# RelayExtension.net
KiCad netlist of a schematic drawn in Altium Designer
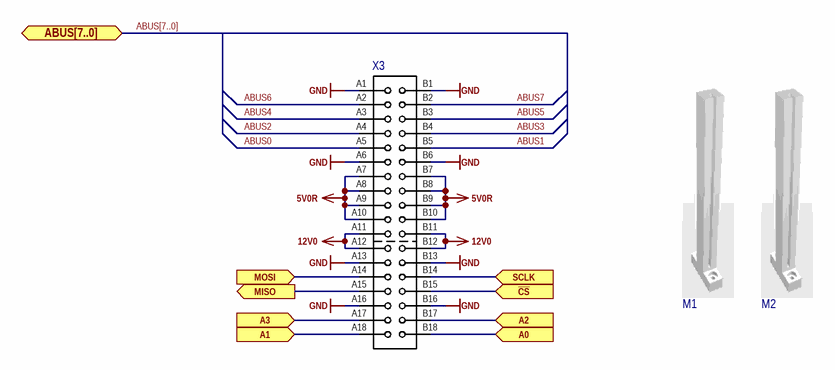
[diagram p0: RelayExtension.SchDoc]

(export (version "E")
  (design (tool "Eeschema 10.0.6"))
  (components
    (comp (ref "M1")
      (value "PCB Support")
      (footprint "PCB Tester Support")
      (fields
        (field (name "07. MANUFACTURER  PART NUMBER") "TBD")
        (field (name "13. CREATED DATE/NAME") "??? / Hören")
      )
      (libsource (lib "PCB-Tester-Board-V1") (part "PCB Tester Support"))
    )
    (comp (ref "M2")
      (value "PCB Support")
      (footprint "PCB Tester Support")
      (fields
        (field (name "07. MANUFACTURER  PART NUMBER") "TBD")
        (field (name "13. CREATED DATE/NAME") "??? / Hören")
      )
      (libsource (lib "PCB-Tester-Board-V1") (part "PCB Tester Support"))
    )
    (comp (ref "X3")
      (value "X")
      (footprint "PCIE-036-02-F-D-TH")
      (description "CONN PCI EXP FMALE 36POS 0.039")
      (fields
        (field (name "02. DISTRIBUTOR PART NUMBER") "SAM10625-ND")
        (field (name "07. MANUFACTURER  PART NUMBER") "PCIE-036-02-F-D-TH")
        (field (name "13. CREATED DATE/NAME") "??? / Hören")
      )
      (libsource (lib "Connectors") (part "PCIE-036-02-F-D-TH"))
    )
  )
  (nets
    (net (code "1") (name "/A0") (class "Default")
      (node (ref "X3") (pin "B18") (pinfunction "B18_B18") (pintype "passive"))
    )
    (net (code "2") (name "/A1") (class "Default")
      (node (ref "X3") (pin "A18") (pinfunction "A18_A18") (pintype "passive"))
    )
    (net (code "3") (name "/A2") (class "Default")
      (node (ref "X3") (pin "B17") (pinfunction "B17_B17") (pintype "passive"))
    )
    (net (code "4") (name "/A3") (class "Default")
      (node (ref "X3") (pin "A17") (pinfunction "A17_A17") (pintype "passive"))
    )
    (net (code "5") (name "/ABUS0") (class "Default")
      (node (ref "X3") (pin "A5") (pinfunction "A5_A5") (pintype "passive"))
    )
    (net (code "6") (name "/ABUS1") (class "Default")
      (node (ref "X3") (pin "B5") (pinfunction "B5_B5") (pintype "passive"))
    )
    (net (code "7") (name "/ABUS2") (class "Default")
      (node (ref "X3") (pin "A4") (pinfunction "A4_A4") (pintype "passive"))
    )
    (net (code "8") (name "/ABUS3") (class "Default")
      (node (ref "X3") (pin "B4") (pinfunction "B4_B4") (pintype "passive"))
    )
    (net (code "9") (name "/ABUS4") (class "Default")
      (node (ref "X3") (pin "A3") (pinfunction "A3_A3") (pintype "passive"))
    )
    (net (code "10") (name "/ABUS5") (class "Default")
      (node (ref "X3") (pin "B3") (pinfunction "B3_B3") (pintype "passive"))
    )
    (net (code "11") (name "/ABUS6") (class "Default")
      (node (ref "X3") (pin "A2") (pinfunction "A2_A2") (pintype "passive"))
    )
    (net (code "12") (name "/ABUS7") (class "Default")
      (node (ref "X3") (pin "B2") (pinfunction "B2_B2") (pintype "passive"))
    )
    (net (code "14") (name "/CS") (class "Default")
      (node (ref "X3") (pin "B15") (pinfunction "B15_B15") (pintype "passive"))
    )
    (net (code "15") (name "/MISO") (class "Default")
      (node (ref "X3") (pin "A15") (pinfunction "A15_A15") (pintype "passive"))
    )
    (net (code "16") (name "/MOSI") (class "Default")
      (node (ref "X3") (pin "A14") (pinfunction "A14_A14") (pintype "passive"))
    )
    (net (code "17") (name "/SCLK") (class "Default")
      (node (ref "X3") (pin "B14") (pinfunction "B14_B14") (pintype "passive"))
    )
    (net (code "18") (name "5V0R") (class "Default")
      (node (ref "X3") (pin "A10") (pinfunction "A10_A10") (pintype "passive"))
      (node (ref "X3") (pin "A7") (pinfunction "A7_A7") (pintype "passive"))
      (node (ref "X3") (pin "A8") (pinfunction "A8_A8") (pintype "passive"))
      (node (ref "X3") (pin "A9") (pinfunction "A9_A9") (pintype "passive"))
      (node (ref "X3") (pin "B10") (pinfunction "B10_B10") (pintype "passive"))
      (node (ref "X3") (pin "B7") (pinfunction "B7_B7") (pintype "passive"))
      (node (ref "X3") (pin "B8") (pinfunction "B8_B8") (pintype "passive"))
      (node (ref "X3") (pin "B9") (pinfunction "B9_B9") (pintype "passive"))
    )
    (net (code "19") (name "12V0") (class "Default")
      (node (ref "X3") (pin "A11") (pinfunction "A11_A11") (pintype "passive"))
      (node (ref "X3") (pin "A12") (pinfunction "A12_A12") (pintype "passive"))
      (node (ref "X3") (pin "B11") (pinfunction "B11_B11") (pintype "passive"))
      (node (ref "X3") (pin "B12") (pinfunction "B12_B12") (pintype "passive"))
    )
    (net (code "20") (name "GND") (class "Default")
      (node (ref "X3") (pin "A1") (pinfunction "A1_A1") (pintype "passive"))
      (node (ref "X3") (pin "A13") (pinfunction "A13_A13") (pintype "passive"))
      (node (ref "X3") (pin "A16") (pinfunction "A16_A16") (pintype "passive"))
      (node (ref "X3") (pin "A6") (pinfunction "A6_A6") (pintype "passive"))
      (node (ref "X3") (pin "B1") (pinfunction "B1_B1") (pintype "passive"))
      (node (ref "X3") (pin "B13") (pinfunction "B13_B13") (pintype "passive"))
      (node (ref "X3") (pin "B16") (pinfunction "B16_B16") (pintype "passive"))
      (node (ref "X3") (pin "B6") (pinfunction "B6_B6") (pintype "passive"))
    )
  )
)
